# CANbus.net
KiCad netlist of a schematic drawn in Altium Designer
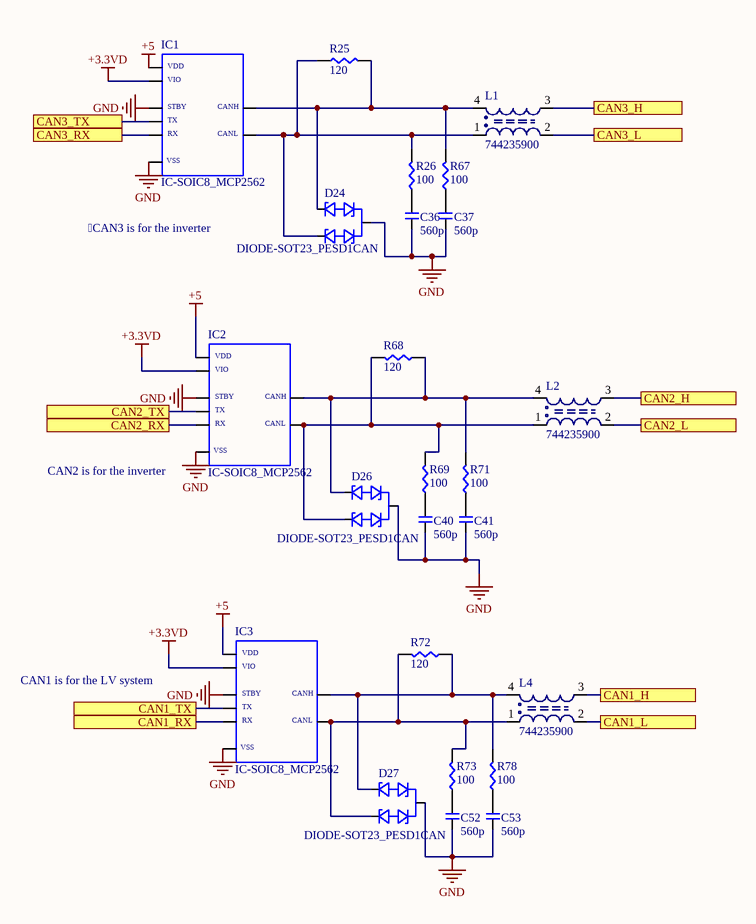
[diagram p0: CANbus.SchDoc]

(export (version "E")
  (design (tool "Eeschema 10.0.6"))
  (components
    (comp (ref "C36")
      (value "560p")
      (footprint "CAP-0603")
      (libsource (lib "ife19_Elec_Library") (part "CAP-0603"))
    )
    (comp (ref "C37")
      (value "560p")
      (footprint "CAP-0603")
      (libsource (lib "ife19_Elec_Library") (part "CAP-0603"))
    )
    (comp (ref "C40")
      (value "560p")
      (footprint "CAP-0603")
      (libsource (lib "ife19_Elec_Library") (part "CAP-0603"))
    )
    (comp (ref "C41")
      (value "560p")
      (footprint "CAP-0603")
      (libsource (lib "ife19_Elec_Library") (part "CAP-0603"))
    )
    (comp (ref "C52")
      (value "560p")
      (footprint "CAP-0603")
      (libsource (lib "ife19_Elec_Library") (part "CAP-0603"))
    )
    (comp (ref "C53")
      (value "560p")
      (footprint "CAP-0603")
      (libsource (lib "ife19_Elec_Library") (part "CAP-0603"))
    )
    (comp (ref "D24")
      (value "DIODE-SOT23_PESD1CAN")
      (footprint "SOT23")
      (libsource (lib "ife19_Elec_Library") (part "DIODE-SOT23_PESD1CAN"))
    )
    (comp (ref "D26")
      (value "DIODE-SOT23_PESD1CAN")
      (footprint "SOT23")
      (libsource (lib "ife19_Elec_Library") (part "DIODE-SOT23_PESD1CAN"))
    )
    (comp (ref "D27")
      (value "DIODE-SOT23_PESD1CAN")
      (footprint "SOT23")
      (libsource (lib "ife19_Elec_Library") (part "DIODE-SOT23_PESD1CAN"))
    )
    (comp (ref "IC1")
      (value "IC-SOIC8_MCP2562")
      (footprint "SOIC8")
      (libsource (lib "ife19_Elec_Library") (part "IC-SOIC8_MCP2562"))
    )
    (comp (ref "IC2")
      (value "IC-SOIC8_MCP2562")
      (footprint "SOIC8")
      (libsource (lib "ife19_Elec_Library") (part "IC-SOIC8_MCP2562"))
    )
    (comp (ref "IC3")
      (value "IC-SOIC8_MCP2562")
      (footprint "SOIC8")
      (libsource (lib "ife19_Elec_Library") (part "IC-SOIC8_MCP2562"))
    )
    (comp (ref "L1")
      (value "744235900")
      (footprint "WE-CNSW 1812")
      (description "SMD Shielded Coupled Inductor WE-CNSW, Z=90 Ohm")
      (fields (field (name "MANUFACTURER") "Wuerth Elektronik"))
      (libsource (lib "Altium Content Vault") (part "WE-IND-INDUCTOR-4Q"))
    )
    (comp (ref "L2")
      (value "744235900")
      (footprint "WE-CNSW 1812")
      (description "SMD Shielded Coupled Inductor WE-CNSW, Z=90 Ohm")
      (fields (field (name "MANUFACTURER") "Wuerth Elektronik"))
      (libsource (lib "Altium Content Vault") (part "WE-IND-INDUCTOR-4Q"))
    )
    (comp (ref "L4")
      (value "744235900")
      (footprint "WE-CNSW 1812")
      (description "SMD Shielded Coupled Inductor WE-CNSW, Z=90 Ohm")
      (fields (field (name "MANUFACTURER") "Wuerth Elektronik"))
      (libsource (lib "Altium Content Vault") (part "WE-IND-INDUCTOR-4Q"))
    )
    (comp (ref "R25")
      (value "120")
      (footprint "RES-0603")
      (libsource (lib "ife19_Elec_Library") (part "RES-0603"))
    )
    (comp (ref "R26")
      (value "100")
      (footprint "RES-0603")
      (libsource (lib "ife19_Elec_Library") (part "RES-0603"))
    )
    (comp (ref "R67")
      (value "100")
      (footprint "RES-0603")
      (libsource (lib "ife19_Elec_Library") (part "RES-0603"))
    )
    (comp (ref "R68")
      (value "120")
      (footprint "RES-0603")
      (libsource (lib "ife19_Elec_Library") (part "RES-0603"))
    )
    (comp (ref "R69")
      (value "100")
      (footprint "RES-0603")
      (libsource (lib "ife19_Elec_Library") (part "RES-0603"))
    )
    (comp (ref "R71")
      (value "100")
      (footprint "RES-0603")
      (libsource (lib "ife19_Elec_Library") (part "RES-0603"))
    )
    (comp (ref "R72")
      (value "120")
      (footprint "RES-0603")
      (libsource (lib "ife19_Elec_Library") (part "RES-0603"))
    )
    (comp (ref "R73")
      (value "100")
      (footprint "RES-0603")
      (libsource (lib "ife19_Elec_Library") (part "RES-0603"))
    )
    (comp (ref "R78")
      (value "100")
      (footprint "RES-0603")
      (libsource (lib "ife19_Elec_Library") (part "RES-0603"))
    )
  )
  (nets
    (net (code "1") (name "+3.3VD") (class "Default")
      (node (ref "IC1") (pin "5") (pinfunction "5_5") (pintype "passive"))
      (node (ref "IC2") (pin "5") (pinfunction "5_5") (pintype "passive"))
      (node (ref "IC3") (pin "5") (pinfunction "5_5") (pintype "passive"))
    )
    (net (code "2") (name "+5") (class "Default")
      (node (ref "IC1") (pin "3") (pinfunction "3_3") (pintype "passive"))
      (node (ref "IC2") (pin "3") (pinfunction "3_3") (pintype "passive"))
      (node (ref "IC3") (pin "3") (pinfunction "3_3") (pintype "passive"))
    )
    (net (code "3") (name "/CAN1_H") (class "Default")
      (node (ref "L4") (pin "3") (pinfunction "3_3") (pintype "passive"))
    )
    (net (code "4") (name "/CAN1_L") (class "Default")
      (node (ref "L4") (pin "2") (pinfunction "2_2") (pintype "passive"))
    )
    (net (code "5") (name "/CAN1_RX") (class "Default")
      (node (ref "IC3") (pin "4") (pinfunction "4_4") (pintype "passive"))
    )
    (net (code "6") (name "/CAN1_TX") (class "Default")
      (node (ref "IC3") (pin "1") (pinfunction "1_1") (pintype "passive"))
    )
    (net (code "7") (name "/CAN2_H") (class "Default")
      (node (ref "L2") (pin "3") (pinfunction "3_3") (pintype "passive"))
    )
    (net (code "8") (name "/CAN2_L") (class "Default")
      (node (ref "L2") (pin "2") (pinfunction "2_2") (pintype "passive"))
    )
    (net (code "9") (name "/CAN2_RX") (class "Default")
      (node (ref "IC2") (pin "4") (pinfunction "4_4") (pintype "passive"))
    )
    (net (code "10") (name "/CAN2_TX") (class "Default")
      (node (ref "IC2") (pin "1") (pinfunction "1_1") (pintype "passive"))
    )
    (net (code "11") (name "/CAN3_H") (class "Default")
      (node (ref "L1") (pin "3") (pinfunction "3_3") (pintype "passive"))
    )
    (net (code "12") (name "/CAN3_L") (class "Default")
      (node (ref "L1") (pin "2") (pinfunction "2_2") (pintype "passive"))
    )
    (net (code "13") (name "/CAN3_RX") (class "Default")
      (node (ref "IC1") (pin "4") (pinfunction "4_4") (pintype "passive"))
    )
    (net (code "14") (name "/CAN3_TX") (class "Default")
      (node (ref "IC1") (pin "1") (pinfunction "1_1") (pintype "passive"))
    )
    (net (code "15") (name "GND") (class "Default")
      (node (ref "C36") (pin "1") (pinfunction "1_1") (pintype "passive"))
      (node (ref "C37") (pin "2") (pinfunction "2_2") (pintype "passive"))
      (node (ref "C40") (pin "1") (pinfunction "1_1") (pintype "passive"))
      (node (ref "C41") (pin "1") (pinfunction "1_1") (pintype "passive"))
      (node (ref "C52") (pin "1") (pinfunction "1_1") (pintype "passive"))
      (node (ref "C53") (pin "1") (pinfunction "1_1") (pintype "passive"))
      (node (ref "D24") (pin "3") (pinfunction "G_3") (pintype "passive"))
      (node (ref "D26") (pin "3") (pinfunction "G_3") (pintype "passive"))
      (node (ref "D27") (pin "3") (pinfunction "G_3") (pintype "passive"))
      (node (ref "IC1") (pin "2") (pinfunction "2_2") (pintype "passive"))
      (node (ref "IC1") (pin "8") (pinfunction "8_8") (pintype "passive"))
      (node (ref "IC2") (pin "2") (pinfunction "2_2") (pintype "passive"))
      (node (ref "IC2") (pin "8") (pinfunction "8_8") (pintype "passive"))
      (node (ref "IC3") (pin "2") (pinfunction "2_2") (pintype "passive"))
      (node (ref "IC3") (pin "8") (pinfunction "8_8") (pintype "passive"))
    )
    (net (code "16") (name "Net-(C36-Pad2)") (class "Default")
      (node (ref "C36") (pin "2") (pinfunction "2_2") (pintype "passive"))
      (node (ref "R26") (pin "1") (pinfunction "1_1") (pintype "passive"))
    )
    (net (code "17") (name "Net-(C37-Pad1)") (class "Default")
      (node (ref "C37") (pin "1") (pinfunction "1_1") (pintype "passive"))
      (node (ref "R67") (pin "1") (pinfunction "1_1") (pintype "passive"))
    )
    (net (code "18") (name "Net-(C40-Pad2)") (class "Default")
      (node (ref "C40") (pin "2") (pinfunction "2_2") (pintype "passive"))
      (node (ref "R69") (pin "1") (pinfunction "1_1") (pintype "passive"))
    )
    (net (code "19") (name "Net-(C41-Pad2)") (class "Default")
      (node (ref "C41") (pin "2") (pinfunction "2_2") (pintype "passive"))
      (node (ref "R71") (pin "1") (pinfunction "1_1") (pintype "passive"))
    )
    (net (code "20") (name "Net-(C52-Pad2)") (class "Default")
      (node (ref "C52") (pin "2") (pinfunction "2_2") (pintype "passive"))
      (node (ref "R73") (pin "1") (pinfunction "1_1") (pintype "passive"))
    )
    (net (code "21") (name "Net-(C53-Pad2)") (class "Default")
      (node (ref "C53") (pin "2") (pinfunction "2_2") (pintype "passive"))
      (node (ref "R78") (pin "1") (pinfunction "1_1") (pintype "passive"))
    )
    (net (code "22") (name "Net-(D24-CAN1)") (class "Default")
      (node (ref "D24") (pin "1") (pinfunction "CAN1_1") (pintype "passive"))
      (node (ref "IC1") (pin "7") (pinfunction "7_7") (pintype "passive"))
      (node (ref "L1") (pin "4") (pinfunction "4_4") (pintype "passive"))
      (node (ref "R25") (pin "2") (pinfunction "2_2") (pintype "passive"))
      (node (ref "R67") (pin "2") (pinfunction "2_2") (pintype "passive"))
    )
    (net (code "23") (name "Net-(D24-CAN2)") (class "Default")
      (node (ref "D24") (pin "2") (pinfunction "CAN2_2") (pintype "passive"))
      (node (ref "IC1") (pin "6") (pinfunction "6_6") (pintype "passive"))
      (node (ref "L1") (pin "1") (pinfunction "1_1") (pintype "passive"))
      (node (ref "R25") (pin "1") (pinfunction "1_1") (pintype "passive"))
      (node (ref "R26") (pin "2") (pinfunction "2_2") (pintype "passive"))
    )
    (net (code "24") (name "Net-(D26-CAN1)") (class "Default")
      (node (ref "D26") (pin "1") (pinfunction "CAN1_1") (pintype "passive"))
      (node (ref "IC2") (pin "7") (pinfunction "7_7") (pintype "passive"))
      (node (ref "L2") (pin "4") (pinfunction "4_4") (pintype "passive"))
      (node (ref "R68") (pin "1") (pinfunction "1_1") (pintype "passive"))
      (node (ref "R71") (pin "2") (pinfunction "2_2") (pintype "passive"))
    )
    (net (code "25") (name "Net-(D26-CAN2)") (class "Default")
      (node (ref "D26") (pin "2") (pinfunction "CAN2_2") (pintype "passive"))
      (node (ref "IC2") (pin "6") (pinfunction "6_6") (pintype "passive"))
      (node (ref "L2") (pin "1") (pinfunction "1_1") (pintype "passive"))
      (node (ref "R68") (pin "2") (pinfunction "2_2") (pintype "passive"))
      (node (ref "R69") (pin "2") (pinfunction "2_2") (pintype "passive"))
    )
    (net (code "26") (name "Net-(D27-CAN1)") (class "Default")
      (node (ref "D27") (pin "1") (pinfunction "CAN1_1") (pintype "passive"))
      (node (ref "IC3") (pin "7") (pinfunction "7_7") (pintype "passive"))
      (node (ref "L4") (pin "4") (pinfunction "4_4") (pintype "passive"))
      (node (ref "R72") (pin "1") (pinfunction "1_1") (pintype "passive"))
      (node (ref "R78") (pin "2") (pinfunction "2_2") (pintype "passive"))
    )
    (net (code "27") (name "Net-(D27-CAN2)") (class "Default")
      (node (ref "D27") (pin "2") (pinfunction "CAN2_2") (pintype "passive"))
      (node (ref "IC3") (pin "6") (pinfunction "6_6") (pintype "passive"))
      (node (ref "L4") (pin "1") (pinfunction "1_1") (pintype "passive"))
      (node (ref "R72") (pin "2") (pinfunction "2_2") (pintype "passive"))
      (node (ref "R73") (pin "2") (pinfunction "2_2") (pintype "passive"))
    )
  )
)
